# main.net
KiCad netlist of a schematic drawn in Altium Designer
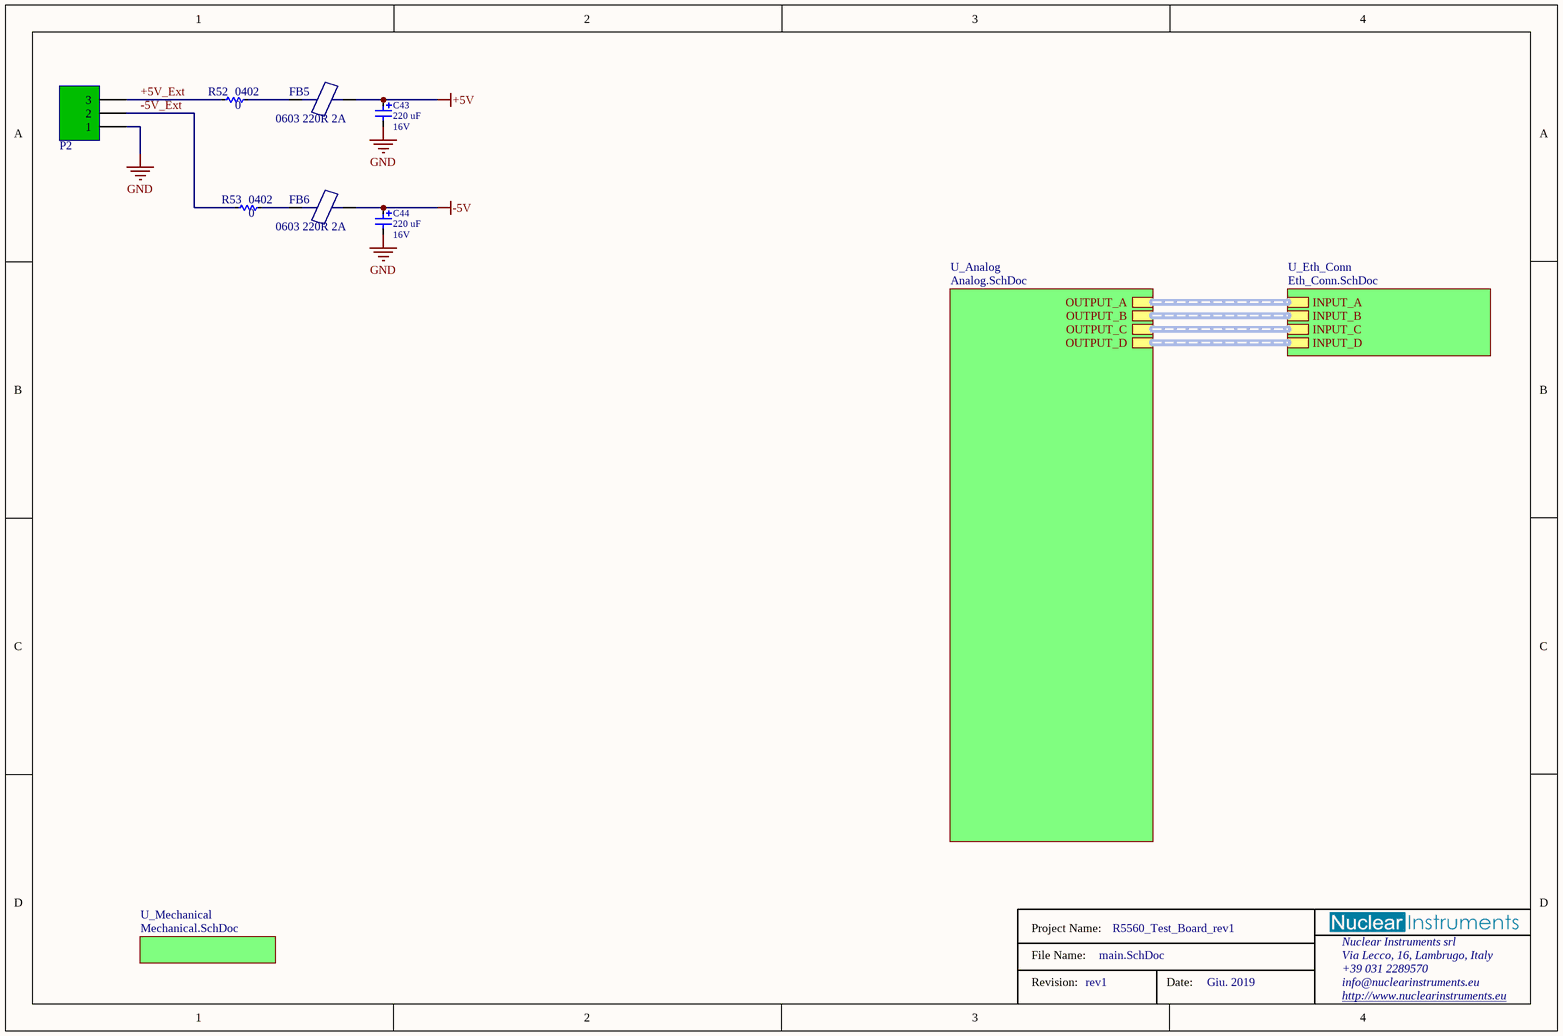
[diagram p0: main.SchDoc]

(export (version "E")
  (design (tool "Eeschema 10.0.6"))
  (components
    (comp (ref "C43")
      (value "220 uF")
      (footprint "CAPELECTSMD_L83_H62")
      (description "Cond. Elettrolitico Allum.220 µF, 16 V")
      (fields (field (name "VOLTAGE") "16V") (field (name "Comment") "CAPELECT"))
      (libsource (lib "Cap_pol__SARAversion-9") (part "CAPELECT_PANASONIC_L83_H62_FK_16V_220u"))
    )
    (comp (ref "C44")
      (value "220 uF")
      (footprint "CAPELECTSMD_L83_H62")
      (description "Cond. Elettrolitico Allum.220 µF, 16 V")
      (fields (field (name "VOLTAGE") "16V") (field (name "Comment") "CAPELECT"))
      (libsource (lib "Cap_pol__SARAversion-9") (part "CAPELECT_PANASONIC_L83_H62_FK_16V_220u"))
    )
    (comp (ref "FB5")
      (value "0603 220R 2A")
      (footprint "FERSMD0603")
      (libsource (lib "Ferrite_Beads__SARAversion-10") (part "FER0603_BLM18EG221SN1D_220R"))
    )
    (comp (ref "FB6")
      (value "0603 220R 2A")
      (footprint "FERSMD0603")
      (libsource (lib "Ferrite_Beads__SARAversion-10") (part "FER0603_BLM18EG221SN1D_220R"))
    )
    (comp (ref "P2")
      (value "3 way 5.08mm pitch")
      (footprint "Wurth_2135_3way_5.08mm_screw")
      (description "Serie 2135- 5.08mm Horizontal Entry Modular w. Rising Cage Clamp WR-TBL")
      (libsource (lib "Board_Wire_Connectors__SARAversion-93") (part "Wurth_2135_3way_5.08mm_screw"))
    )
    (comp (ref "R52")
      (value "0402")
      (footprint "RESSMD0402")
      (fields (field (name "ALTIUM_VALUE") "0"))
      (libsource (lib "0402_Resistors__SARAversion-52") (part "RES0402-0R"))
    )
    (comp (ref "R53")
      (value "0402")
      (footprint "RESSMD0402")
      (fields (field (name "ALTIUM_VALUE") "0"))
      (libsource (lib "0402_Resistors__SARAversion-52") (part "RES0402-0R"))
    )
  )
  (nets
    (net (code "1") (name "+5V") (class "Default")
      (node (ref "C43") (pin "1") (pinfunction "1_1") (pintype "passive"))
      (node (ref "FB5") (pin "2") (pinfunction "2_2") (pintype "passive"))
    )
    (net (code "2") (name "-5V") (class "Default")
      (node (ref "C44") (pin "1") (pinfunction "1_1") (pintype "passive"))
      (node (ref "FB6") (pin "2") (pinfunction "2_2") (pintype "passive"))
    )
    (net (code "3") (name "/+5V_Ext") (class "Default")
      (node (ref "P2") (pin "3") (pinfunction "3_3") (pintype "passive"))
      (node (ref "R52") (pin "1") (pinfunction "1_1") (pintype "passive"))
    )
    (net (code "4") (name "/-5V_Ext") (class "Default")
      (node (ref "P2") (pin "2") (pinfunction "2_2") (pintype "passive"))
      (node (ref "R53") (pin "1") (pinfunction "1_1") (pintype "passive"))
    )
    (net (code "9") (name "GND") (class "Default")
      (node (ref "C43") (pin "2") (pinfunction "2_2") (pintype "passive"))
      (node (ref "C44") (pin "2") (pinfunction "2_2") (pintype "passive"))
      (node (ref "P2") (pin "1") (pinfunction "1_1") (pintype "passive"))
    )
    (net (code "10") (name "Net-(FB5-Pad1)") (class "Default")
      (node (ref "FB5") (pin "1") (pinfunction "1_1") (pintype "passive"))
      (node (ref "R52") (pin "2") (pinfunction "2_2") (pintype "passive"))
    )
    (net (code "11") (name "Net-(FB6-Pad1)") (class "Default")
      (node (ref "FB6") (pin "1") (pinfunction "1_1") (pintype "passive"))
      (node (ref "R53") (pin "2") (pinfunction "2_2") (pintype "passive"))
    )
  )
)
